# TSMPC.net
KiCad netlist of a schematic drawn in EAGLE
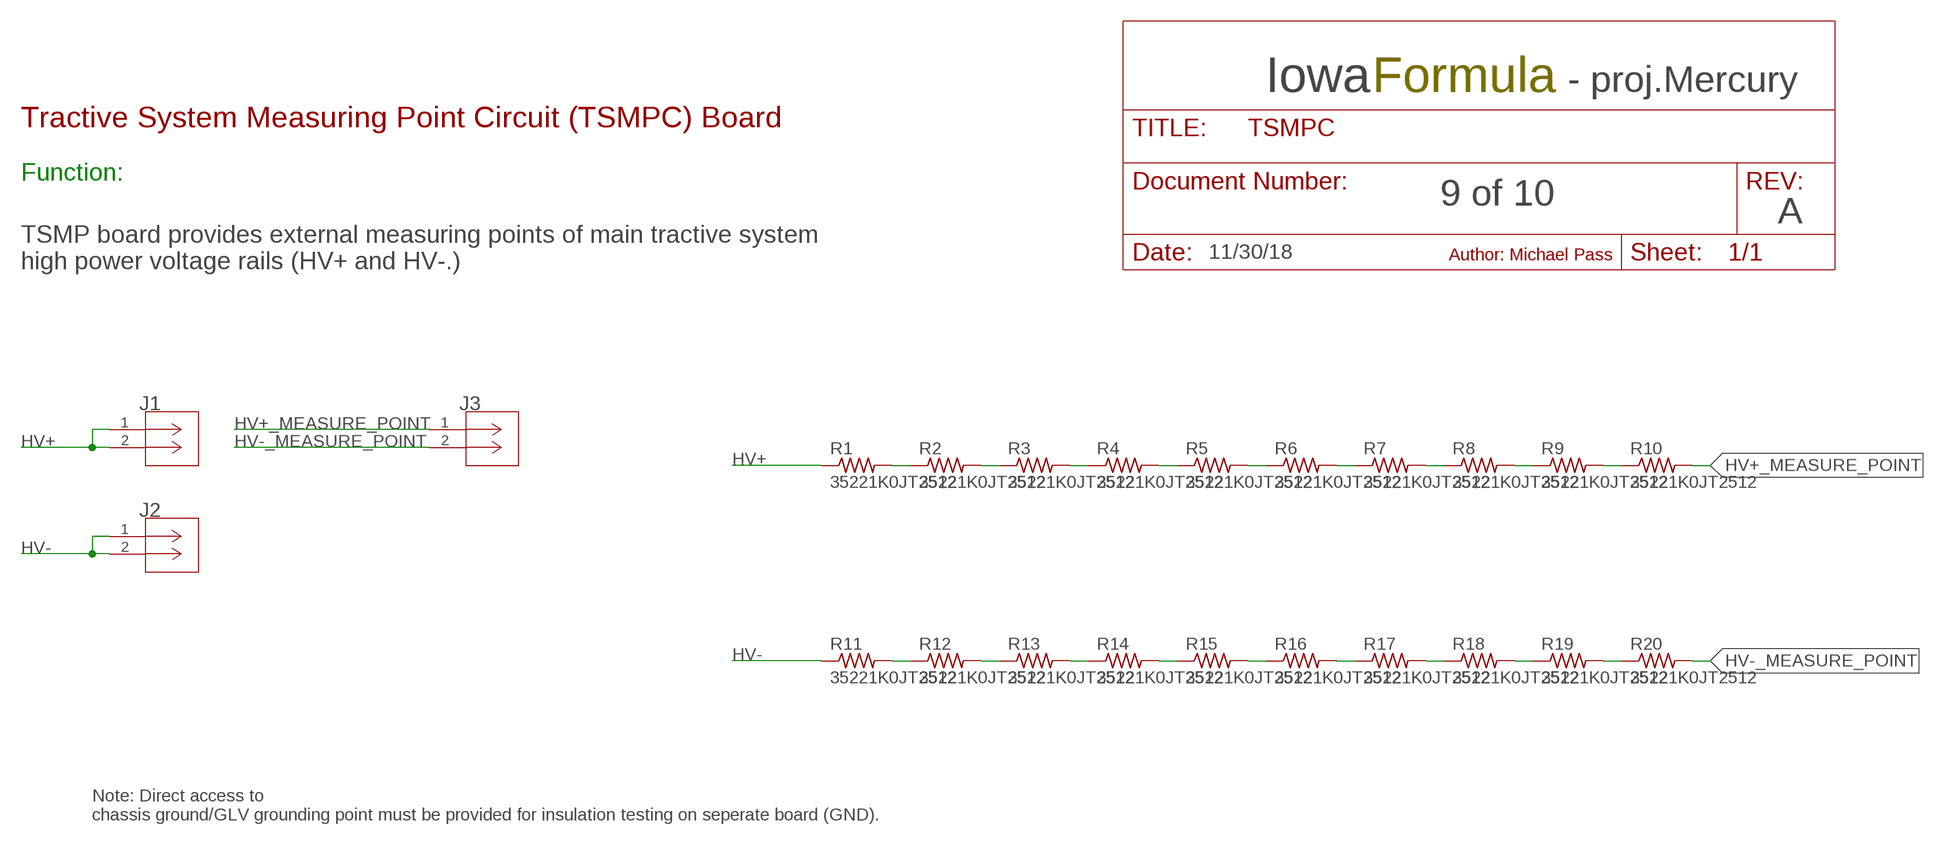
[diagram p0: schematic, sheet 1]

(export (version "E")
  (design (tool "Eeschema 10.0.6"))
  (components
    (comp (ref "J1")
      (value "2P_1-770166-0")
      (footprint "eagle-import:CON2_1X2_P163_VMNL-1MTG")
      (fields (field (name "MANUFACTURER_PART_NUMBER") "17701660"))
      (libsource (lib "eagle-import") (part "2P_1-770166-0"))
    )
    (comp (ref "J2")
      (value "2P_1-770166-0")
      (footprint "eagle-import:CON2_1X2_P163_VMNL-1MTG")
      (fields (field (name "MANUFACTURER_PART_NUMBER") "17701660"))
      (libsource (lib "eagle-import") (part "2P_1-770166-0"))
    )
    (comp (ref "J3")
      (value "2P_1-770166-0")
      (footprint "eagle-import:CON2_1X2_P163_VMNL-1MTG")
      (fields (field (name "MANUFACTURER_PART_NUMBER") "17701660"))
      (libsource (lib "eagle-import") (part "2P_1-770166-0"))
    )
    (comp (ref "R1")
      (value "35221K0JT2512")
      (footprint "eagle-import:R2512")
      (libsource (lib "eagle-import") (part "35221K0JT2512"))
    )
    (comp (ref "R2")
      (value "35221K0JT2512")
      (footprint "eagle-import:R2512")
      (libsource (lib "eagle-import") (part "35221K0JT2512"))
    )
    (comp (ref "R3")
      (value "35221K0JT2512")
      (footprint "eagle-import:R2512")
      (libsource (lib "eagle-import") (part "35221K0JT2512"))
    )
    (comp (ref "R4")
      (value "35221K0JT2512")
      (footprint "eagle-import:R2512")
      (libsource (lib "eagle-import") (part "35221K0JT2512"))
    )
    (comp (ref "R5")
      (value "35221K0JT2512")
      (footprint "eagle-import:R2512")
      (libsource (lib "eagle-import") (part "35221K0JT2512"))
    )
    (comp (ref "R6")
      (value "35221K0JT2512")
      (footprint "eagle-import:R2512")
      (libsource (lib "eagle-import") (part "35221K0JT2512"))
    )
    (comp (ref "R7")
      (value "35221K0JT2512")
      (footprint "eagle-import:R2512")
      (libsource (lib "eagle-import") (part "35221K0JT2512"))
    )
    (comp (ref "R8")
      (value "35221K0JT2512")
      (footprint "eagle-import:R2512")
      (libsource (lib "eagle-import") (part "35221K0JT2512"))
    )
    (comp (ref "R9")
      (value "35221K0JT2512")
      (footprint "eagle-import:R2512")
      (libsource (lib "eagle-import") (part "35221K0JT2512"))
    )
    (comp (ref "R10")
      (value "35221K0JT2512")
      (footprint "eagle-import:R2512")
      (libsource (lib "eagle-import") (part "35221K0JT2512"))
    )
    (comp (ref "R11")
      (value "35221K0JT2512")
      (footprint "eagle-import:R2512")
      (libsource (lib "eagle-import") (part "35221K0JT2512"))
    )
    (comp (ref "R12")
      (value "35221K0JT2512")
      (footprint "eagle-import:R2512")
      (libsource (lib "eagle-import") (part "35221K0JT2512"))
    )
    (comp (ref "R13")
      (value "35221K0JT2512")
      (footprint "eagle-import:R2512")
      (libsource (lib "eagle-import") (part "35221K0JT2512"))
    )
    (comp (ref "R14")
      (value "35221K0JT2512")
      (footprint "eagle-import:R2512")
      (libsource (lib "eagle-import") (part "35221K0JT2512"))
    )
    (comp (ref "R15")
      (value "35221K0JT2512")
      (footprint "eagle-import:R2512")
      (libsource (lib "eagle-import") (part "35221K0JT2512"))
    )
    (comp (ref "R16")
      (value "35221K0JT2512")
      (footprint "eagle-import:R2512")
      (libsource (lib "eagle-import") (part "35221K0JT2512"))
    )
    (comp (ref "R17")
      (value "35221K0JT2512")
      (footprint "eagle-import:R2512")
      (libsource (lib "eagle-import") (part "35221K0JT2512"))
    )
    (comp (ref "R18")
      (value "35221K0JT2512")
      (footprint "eagle-import:R2512")
      (libsource (lib "eagle-import") (part "35221K0JT2512"))
    )
    (comp (ref "R19")
      (value "35221K0JT2512")
      (footprint "eagle-import:R2512")
      (libsource (lib "eagle-import") (part "35221K0JT2512"))
    )
    (comp (ref "R20")
      (value "35221K0JT2512")
      (footprint "eagle-import:R2512")
      (libsource (lib "eagle-import") (part "35221K0JT2512"))
    )
  )
  (nets
    (net (code "1") (name "/HV+") (class "Default")
      (node (ref "J1") (pin "1") (pinfunction "1_1") (pintype "passive"))
      (node (ref "J1") (pin "2") (pinfunction "2_2") (pintype "passive"))
      (node (ref "R1") (pin "1") (pinfunction "1_1") (pintype "passive"))
    )
    (net (code "2") (name "/HV-") (class "Default")
      (node (ref "J2") (pin "1") (pinfunction "1_1") (pintype "passive"))
      (node (ref "J2") (pin "2") (pinfunction "2_2") (pintype "passive"))
      (node (ref "R11") (pin "1") (pinfunction "1_1") (pintype "passive"))
    )
    (net (code "3") (name "HV+_MEASURE_POINT") (class "Default")
      (node (ref "J3") (pin "1") (pinfunction "1_1") (pintype "passive"))
      (node (ref "R10") (pin "2") (pinfunction "2_2") (pintype "passive"))
    )
    (net (code "4") (name "HV-_MEASURE_POINT") (class "Default")
      (node (ref "J3") (pin "2") (pinfunction "2_2") (pintype "passive"))
      (node (ref "R20") (pin "2") (pinfunction "2_2") (pintype "passive"))
    )
    (net (code "5") (name "Net-(R1-Pad2)") (class "Default")
      (node (ref "R1") (pin "2") (pinfunction "2_2") (pintype "passive"))
      (node (ref "R2") (pin "1") (pinfunction "1_1") (pintype "passive"))
    )
    (net (code "6") (name "Net-(R2-Pad2)") (class "Default")
      (node (ref "R2") (pin "2") (pinfunction "2_2") (pintype "passive"))
      (node (ref "R3") (pin "1") (pinfunction "1_1") (pintype "passive"))
    )
    (net (code "7") (name "Net-(R3-Pad2)") (class "Default")
      (node (ref "R3") (pin "2") (pinfunction "2_2") (pintype "passive"))
      (node (ref "R4") (pin "1") (pinfunction "1_1") (pintype "passive"))
    )
    (net (code "8") (name "Net-(R4-Pad2)") (class "Default")
      (node (ref "R4") (pin "2") (pinfunction "2_2") (pintype "passive"))
      (node (ref "R5") (pin "1") (pinfunction "1_1") (pintype "passive"))
    )
    (net (code "9") (name "Net-(R5-Pad2)") (class "Default")
      (node (ref "R5") (pin "2") (pinfunction "2_2") (pintype "passive"))
      (node (ref "R6") (pin "1") (pinfunction "1_1") (pintype "passive"))
    )
    (net (code "10") (name "Net-(R6-Pad2)") (class "Default")
      (node (ref "R6") (pin "2") (pinfunction "2_2") (pintype "passive"))
      (node (ref "R7") (pin "1") (pinfunction "1_1") (pintype "passive"))
    )
    (net (code "11") (name "Net-(R7-Pad2)") (class "Default")
      (node (ref "R7") (pin "2") (pinfunction "2_2") (pintype "passive"))
      (node (ref "R8") (pin "1") (pinfunction "1_1") (pintype "passive"))
    )
    (net (code "12") (name "Net-(R8-Pad2)") (class "Default")
      (node (ref "R8") (pin "2") (pinfunction "2_2") (pintype "passive"))
      (node (ref "R9") (pin "1") (pinfunction "1_1") (pintype "passive"))
    )
    (net (code "13") (name "Net-(R10-Pad1)") (class "Default")
      (node (ref "R10") (pin "1") (pinfunction "1_1") (pintype "passive"))
      (node (ref "R9") (pin "2") (pinfunction "2_2") (pintype "passive"))
    )
    (net (code "14") (name "Net-(R11-Pad2)") (class "Default")
      (node (ref "R11") (pin "2") (pinfunction "2_2") (pintype "passive"))
      (node (ref "R12") (pin "1") (pinfunction "1_1") (pintype "passive"))
    )
    (net (code "15") (name "Net-(R12-Pad2)") (class "Default")
      (node (ref "R12") (pin "2") (pinfunction "2_2") (pintype "passive"))
      (node (ref "R13") (pin "1") (pinfunction "1_1") (pintype "passive"))
    )
    (net (code "16") (name "Net-(R13-Pad2)") (class "Default")
      (node (ref "R13") (pin "2") (pinfunction "2_2") (pintype "passive"))
      (node (ref "R14") (pin "1") (pinfunction "1_1") (pintype "passive"))
    )
    (net (code "17") (name "Net-(R14-Pad2)") (class "Default")
      (node (ref "R14") (pin "2") (pinfunction "2_2") (pintype "passive"))
      (node (ref "R15") (pin "1") (pinfunction "1_1") (pintype "passive"))
    )
    (net (code "18") (name "Net-(R15-Pad2)") (class "Default")
      (node (ref "R15") (pin "2") (pinfunction "2_2") (pintype "passive"))
      (node (ref "R16") (pin "1") (pinfunction "1_1") (pintype "passive"))
    )
    (net (code "19") (name "Net-(R16-Pad2)") (class "Default")
      (node (ref "R16") (pin "2") (pinfunction "2_2") (pintype "passive"))
      (node (ref "R17") (pin "1") (pinfunction "1_1") (pintype "passive"))
    )
    (net (code "20") (name "Net-(R17-Pad2)") (class "Default")
      (node (ref "R17") (pin "2") (pinfunction "2_2") (pintype "passive"))
      (node (ref "R18") (pin "1") (pinfunction "1_1") (pintype "passive"))
    )
    (net (code "21") (name "Net-(R18-Pad2)") (class "Default")
      (node (ref "R18") (pin "2") (pinfunction "2_2") (pintype "passive"))
      (node (ref "R19") (pin "1") (pinfunction "1_1") (pintype "passive"))
    )
    (net (code "22") (name "Net-(R19-Pad2)") (class "Default")
      (node (ref "R19") (pin "2") (pinfunction "2_2") (pintype "passive"))
      (node (ref "R20") (pin "1") (pinfunction "1_1") (pintype "passive"))
    )
  )
)
